# power_section.net
KiCad netlist of a schematic drawn in Altium Designer
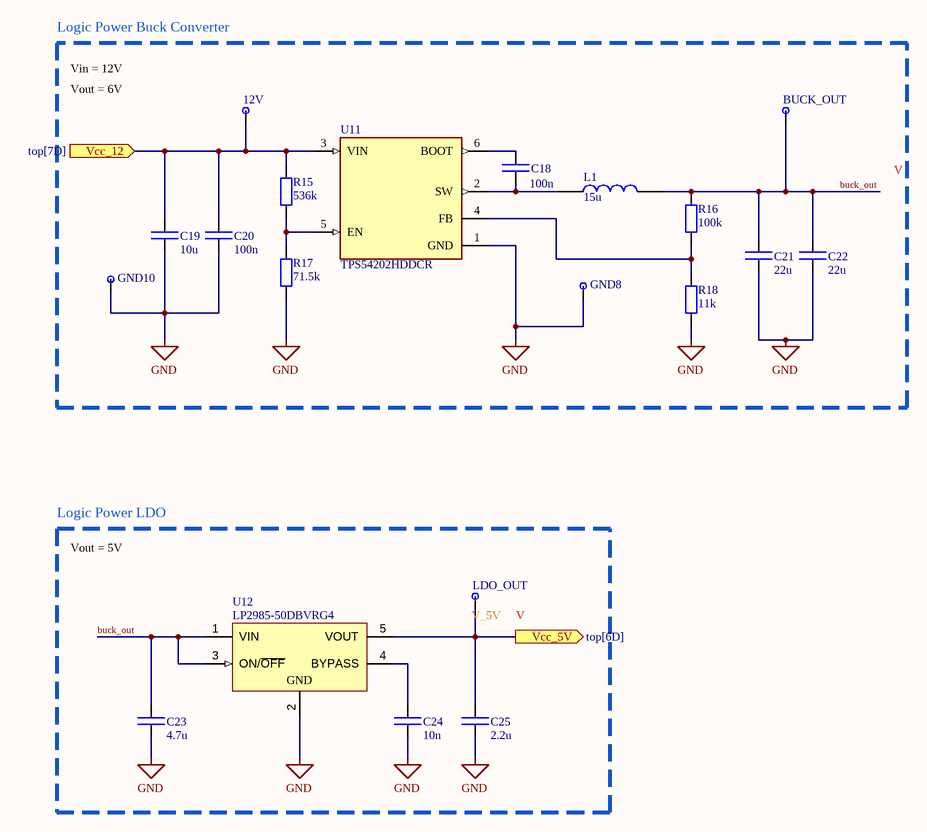
[diagram p0: power_section.SchDoc]

(export (version "E")
  (design (tool "Eeschema 10.0.6"))
  (components
    (comp (ref "12V")
      (value "TestPoint")
      (footprint "TestPoint_SMT")
      (description "Test Point")
      (libsource (lib "INT_lib") (part "TestPoint"))
    )
    (comp (ref "BUCK_OUT")
      (value "TestPoint")
      (footprint "TestPoint_SMT")
      (description "Test Point")
      (libsource (lib "INT_lib") (part "TestPoint"))
    )
    (comp (ref "C18")
      (value "100n")
      (footprint "CAP_IPC_0805_133A")
      (libsource (lib "INT_lib") (part "Capacitor"))
    )
    (comp (ref "C19")
      (value "10u")
      (footprint "CAP_IPC_0805_133A")
      (libsource (lib "INT_lib") (part "Capacitor"))
    )
    (comp (ref "C20")
      (value "100n")
      (footprint "CAP_IPC_0805_133A")
      (libsource (lib "INT_lib") (part "Capacitor"))
    )
    (comp (ref "C21")
      (value "22u")
      (footprint "CAP_IPC_0805_133A")
      (libsource (lib "INT_lib") (part "Capacitor"))
    )
    (comp (ref "C22")
      (value "22u")
      (footprint "CAP_IPC_0805_133A")
      (libsource (lib "INT_lib") (part "Capacitor"))
    )
    (comp (ref "C23")
      (value "4.7u")
      (footprint "CAP_IPC_0805_133A")
      (fields (field (name "VOLTAGE") "16V"))
      (libsource (lib "INT_lib") (part "Capacitor"))
    )
    (comp (ref "C24")
      (value "10n")
      (footprint "CAP_IPC_0805_133A")
      (libsource (lib "INT_lib") (part "Capacitor"))
    )
    (comp (ref "C25")
      (value "2.2u")
      (footprint "CAP_IPC_0805_133A")
      (libsource (lib "INT_lib") (part "Capacitor"))
    )
    (comp (ref "GND8")
      (value "TestPoint")
      (footprint "TestPoint_SMT")
      (description "Test Point")
      (libsource (lib "INT_lib") (part "TestPoint"))
    )
    (comp (ref "GND10")
      (value "TestPoint")
      (footprint "TestPoint_SMT")
      (description "Test Point")
      (libsource (lib "INT_lib") (part "TestPoint"))
    )
    (comp (ref "L1")
      (value "15u")
      (footprint "INDPM7373X455N")
      (description "Fixed Inductors 15uH 2.2A SMT")
      (fields (field (name "MANUFACTURER_PART_NUMBER") "46153C"))
      (libsource (lib "INT_lib") (part "46153C_inductor"))
    )
    (comp (ref "LDO_OUT")
      (value "TestPoint")
      (footprint "TestPoint_SMT")
      (description "Test Point")
      (libsource (lib "INT_lib") (part "TestPoint"))
    )
    (comp (ref "R15")
      (value "536k")
      (footprint "RES_VJ_0402_MD")
      (libsource (lib "INT_lib") (part "Resistor"))
    )
    (comp (ref "R16")
      (value "100k")
      (footprint "RES_VJ_0402_MD")
      (libsource (lib "INT_lib") (part "Resistor"))
    )
    (comp (ref "R17")
      (value "71.5k")
      (footprint "RES_VJ_0402_MD")
      (libsource (lib "INT_lib") (part "Resistor"))
    )
    (comp (ref "R18")
      (value "11k")
      (footprint "RES_VJ_0402_MD")
      (libsource (lib "INT_lib") (part "Resistor"))
    )
    (comp (ref "U11")
      (value "TPS54202HDDCR")
      (footprint "TPS54202HDDCR")
      (description "IC REG BUCK ADJ 2A TSOT23-6")
      (libsource (lib "INT_lib") (part "TPS54202HDDCR"))
    )
    (comp (ref "U12")
      (value "LP2985-50DBVRG4")
      (footprint "LP2985-50DBVRG4")
      (fields (field (name "MANUFACTURER") "Texas Instruments"))
      (libsource (lib "INT_lib") (part "LP2985-50DBVRG4"))
    )
  )
  (nets
    (net (code "1") (name "/Vcc_5V") (class "Default")
      (node (ref "C25") (pin "1") (pinfunction "1_1") (pintype "passive"))
      (node (ref "LDO_OUT") (pin "1") (pinfunction "1_1") (pintype "passive"))
      (node (ref "U12") (pin "5") (pinfunction "VOUT_5") (pintype "passive"))
    )
    (net (code "2") (name "/Vcc_12") (class "Default")
      (node (ref "12V") (pin "1") (pinfunction "1_1") (pintype "passive"))
      (node (ref "C19") (pin "1") (pinfunction "1_1") (pintype "passive"))
      (node (ref "C20") (pin "1") (pinfunction "1_1") (pintype "passive"))
      (node (ref "R15") (pin "1") (pinfunction "1_1") (pintype "passive"))
      (node (ref "U11") (pin "3") (pinfunction "VIN_3") (pintype "input"))
    )
    (net (code "3") (name "/buck_out") (class "Default")
      (node (ref "BUCK_OUT") (pin "1") (pinfunction "1_1") (pintype "passive"))
      (node (ref "C21") (pin "1") (pinfunction "1_1") (pintype "passive"))
      (node (ref "C22") (pin "1") (pinfunction "1_1") (pintype "passive"))
      (node (ref "C23") (pin "1") (pinfunction "1_1") (pintype "passive"))
      (node (ref "L1") (pin "2") (pinfunction "2_2") (pintype "passive"))
      (node (ref "R16") (pin "1") (pinfunction "1_1") (pintype "passive"))
      (node (ref "U12") (pin "1") (pinfunction "VIN_1") (pintype "power_in"))
      (node (ref "U12") (pin "3") (pinfunction "ON/~{OFF}_3") (pintype "input"))
    )
    (net (code "4") (name "GND") (class "Default")
      (node (ref "C19") (pin "2") (pinfunction "2_2") (pintype "passive"))
      (node (ref "C20") (pin "2") (pinfunction "2_2") (pintype "passive"))
      (node (ref "C21") (pin "2") (pinfunction "2_2") (pintype "passive"))
      (node (ref "C22") (pin "2") (pinfunction "2_2") (pintype "passive"))
      (node (ref "C23") (pin "2") (pinfunction "2_2") (pintype "passive"))
      (node (ref "C24") (pin "2") (pinfunction "2_2") (pintype "passive"))
      (node (ref "C25") (pin "2") (pinfunction "2_2") (pintype "passive"))
      (node (ref "GND10") (pin "1") (pinfunction "1_1") (pintype "passive"))
      (node (ref "GND8") (pin "1") (pinfunction "1_1") (pintype "passive"))
      (node (ref "R17") (pin "2") (pinfunction "2_2") (pintype "passive"))
      (node (ref "R18") (pin "2") (pinfunction "2_2") (pintype "passive"))
      (node (ref "U11") (pin "1") (pinfunction "GND_1") (pintype "power_in"))
      (node (ref "U12") (pin "2") (pinfunction "GND_2") (pintype "power_in"))
    )
    (net (code "5") (name "Net-(U11-BOOT)") (class "Default")
      (node (ref "C18") (pin "1") (pinfunction "1_1") (pintype "passive"))
      (node (ref "U11") (pin "6") (pinfunction "BOOT_6") (pintype "output"))
    )
    (net (code "6") (name "Net-(U11-EN)") (class "Default")
      (node (ref "R15") (pin "2") (pinfunction "2_2") (pintype "passive"))
      (node (ref "R17") (pin "1") (pinfunction "1_1") (pintype "passive"))
      (node (ref "U11") (pin "5") (pinfunction "EN_5") (pintype "input"))
    )
    (net (code "7") (name "Net-(U11-FB)") (class "Default")
      (node (ref "R16") (pin "2") (pinfunction "2_2") (pintype "passive"))
      (node (ref "R18") (pin "1") (pinfunction "1_1") (pintype "passive"))
      (node (ref "U11") (pin "4") (pinfunction "FB_4") (pintype "passive"))
    )
    (net (code "8") (name "Net-(U11-SW)") (class "Default")
      (node (ref "C18") (pin "2") (pinfunction "2_2") (pintype "passive"))
      (node (ref "L1") (pin "1") (pinfunction "1_1") (pintype "passive"))
      (node (ref "U11") (pin "2") (pinfunction "SW_2") (pintype "output"))
    )
    (net (code "9") (name "Net-(U12-BYPASS)") (class "Default")
      (node (ref "C24") (pin "1") (pinfunction "1_1") (pintype "passive"))
      (node (ref "U12") (pin "4") (pinfunction "BYPASS_4") (pintype "passive"))
    )
  )
)
